# STM8S003F3P6_RF_1RELAY_LEARN_CODE.net
KiCad netlist of a schematic drawn in Altium Designer
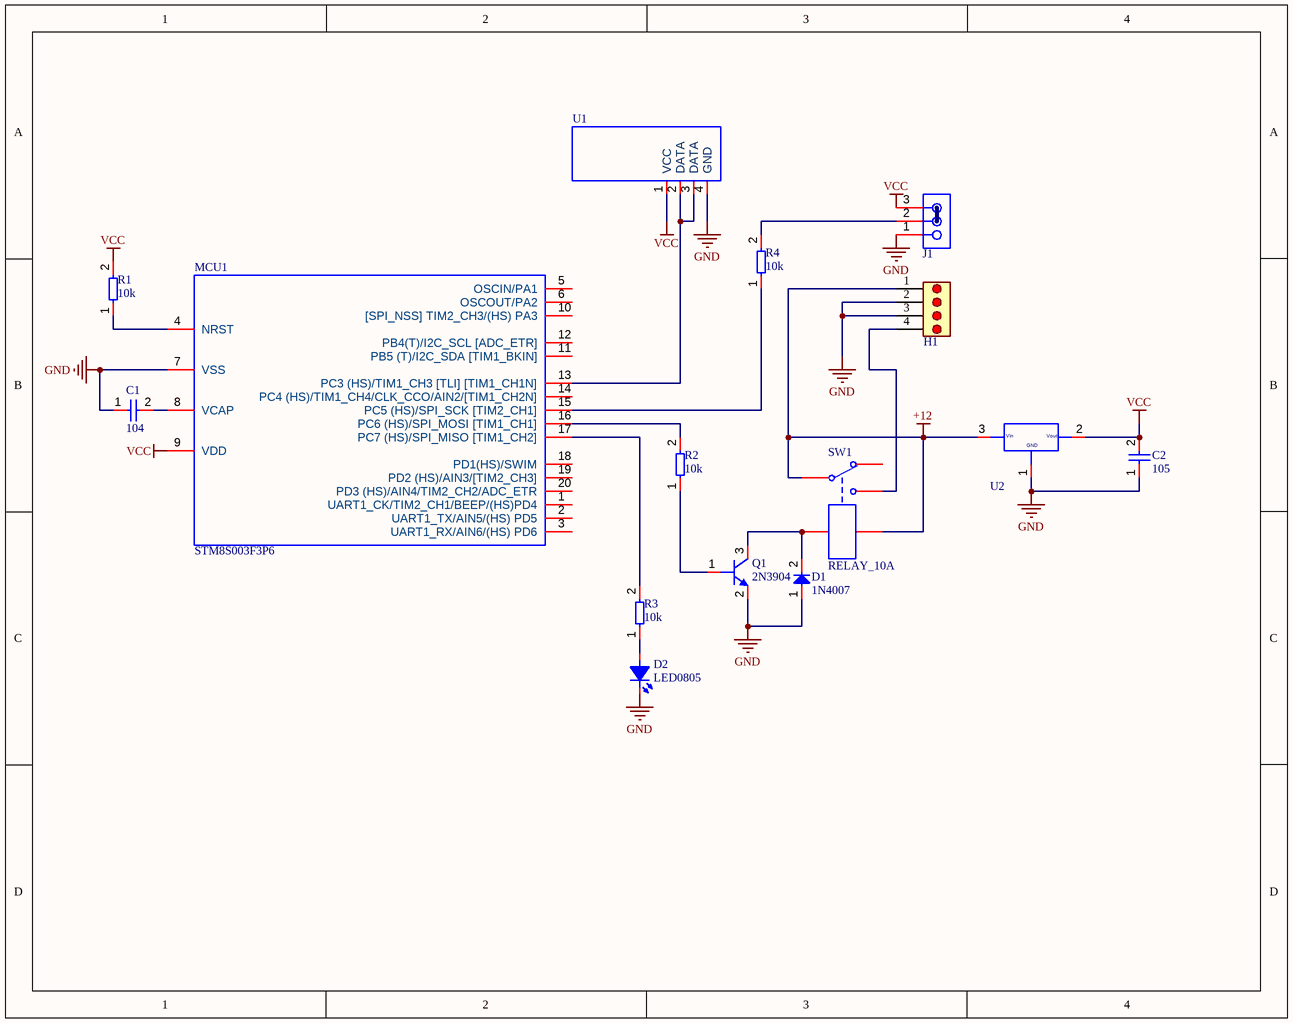
[diagram p0: STM8S003F3P6_RF_1RELAY_LEARN_CODE.SchDoc]

(export (version "E")
  (design (tool "Eeschema 10.0.6"))
  (components
    (comp (ref "C1") (value "104") (footprint "C0805") (libsource (lib "Lib31082020") (part "C0805")))
    (comp (ref "C2") (value "105") (footprint "C1206") (libsource (lib "Lib31082020") (part "C1206")))
    (comp (ref "D1")
      (value "1N4007")
      (footprint "DO-214AC(SMA)")
      (libsource (lib "Lib31082020") (part "Diode 1N4007-DO214AC(SMA)"))
    )
    (comp (ref "D2")
      (value "LED0805")
      (footprint "L0805RED")
      (libsource (lib "Lib31082020") (part "LED0805"))
    )
    (comp (ref "H1")
      (value "Header 4")
      (footprint "HEADER 4")
      (libsource (lib "Library 3D") (part "Header 4"))
    )
    (comp (ref "J1")
      (value "Header 3x1 TH Pitch 2.54mm")
      (footprint "Header 3x1 TH Pitch 2.54mm")
      (libsource (lib "Lib31082020") (part "Header 3x1 TH Pitch 2.54mm"))
    )
    (comp (ref "MCU1")
      (value "STM8S003F3P6")
      (footprint "TSSOP20_0.65_4.4")
      (libsource (lib "Lib31082020") (part "STM8S003F3P6"))
    )
    (comp (ref "Q1")
      (value "2N3904")
      (footprint "SOT23-3")
      (libsource (lib "Lib31082020") (part "2N3904 (SOT-23)"))
    )
    (comp (ref "R1") (value "10k") (footprint "R0805") (libsource (lib "Lib31082020") (part "Resistor SMD")))
    (comp (ref "R2") (value "10k") (footprint "R0805") (libsource (lib "Lib31082020") (part "Resistor SMD")))
    (comp (ref "R3") (value "10k") (footprint "R0805") (libsource (lib "Lib31082020") (part "Resistor SMD")))
    (comp (ref "R4") (value "10k") (footprint "R0805") (libsource (lib "Lib31082020") (part "Resistor SMD")))
    (comp (ref "SW1")
      (value "RELAY_10A")
      (footprint "RELAY_10A_5PIN")
      (libsource (lib "Lib31082020") (part "RELAY_10A"))
    )
    (comp (ref "U1")
      (value "RF433_315_RECEVICE")
      (footprint "RF433_315_RECEVICE")
      (libsource (lib "Lib31082020") (part "RF433_315"))
    )
    (comp (ref "U2")
      (value "AMS1117")
      (footprint "SOT223-3")
      (libsource (lib "Lib31082020") (part "AMS1117(SOT-223)"))
    )
  )
  (nets
    (net (code "1") (name "+12") (class "Default")
      (node (ref "H1") (pin "1") (pinfunction "1_1") (pintype "passive"))
      (node (ref "SW1") (pin "2") (pinfunction "2_2") (pintype "passive"))
      (node (ref "SW1") (pin "3") (pinfunction "3_3") (pintype "passive"))
      (node (ref "U2") (pin "3") (pinfunction "3_3") (pintype "passive"))
    )
    (net (code "2") (name "GND") (class "Default")
      (node (ref "C1") (pin "1") (pinfunction "1_1") (pintype "passive"))
      (node (ref "C2") (pin "1") (pinfunction "1_1") (pintype "passive"))
      (node (ref "D1") (pin "1") (pinfunction "1_1") (pintype "passive"))
      (node (ref "D2") (pin "2") (pinfunction "K_2") (pintype "passive"))
      (node (ref "H1") (pin "2") (pinfunction "2_2") (pintype "passive"))
      (node (ref "H1") (pin "3") (pinfunction "3_3") (pintype "passive"))
      (node (ref "J1") (pin "1") (pinfunction "1_1") (pintype "passive"))
      (node (ref "MCU1") (pin "7") (pinfunction "VSS_7") (pintype "passive"))
      (node (ref "Q1") (pin "2") (pinfunction "E_2") (pintype "passive"))
      (node (ref "U1") (pin "4") (pinfunction "GND_4") (pintype "passive"))
      (node (ref "U2") (pin "1") (pinfunction "1_1") (pintype "passive"))
    )
    (net (code "3") (name "Net-(D2-A)") (class "Default")
      (node (ref "D2") (pin "1") (pinfunction "A_1") (pintype "passive"))
      (node (ref "R3") (pin "1") (pinfunction "1_1") (pintype "passive"))
    )
    (net (code "4") (name "Net-(H1-Pad4)") (class "Default")
      (node (ref "H1") (pin "4") (pinfunction "4_4") (pintype "passive"))
      (node (ref "SW1") (pin "5") (pinfunction "5_5") (pintype "passive"))
    )
    (net (code "5") (name "Net-(J1-Pad2)") (class "Default")
      (node (ref "J1") (pin "2") (pinfunction "2_2") (pintype "passive"))
      (node (ref "R4") (pin "2") (pinfunction "2_2") (pintype "passive"))
    )
    (net (code "6") (name "Net-(MCU1-NRST)") (class "Default")
      (node (ref "MCU1") (pin "4") (pinfunction "NRST_4") (pintype "passive"))
      (node (ref "R1") (pin "1") (pinfunction "1_1") (pintype "passive"))
    )
    (net (code "7") (name "Net-(MCU1-PC3_(HS){slash}TIM1_CH3_[TLI]_[TIM1_CH1N])") (class "Default")
      (node (ref "MCU1") (pin "13") (pinfunction "PC3_(HS)/TIM1_CH3_[TLI]_[TIM1_CH1N]_13") (pintype "passive"))
      (node (ref "U1") (pin "2") (pinfunction "DATA_2") (pintype "passive"))
      (node (ref "U1") (pin "3") (pinfunction "DATA_3") (pintype "passive"))
    )
    (net (code "8") (name "Net-(MCU1-PC5_(HS){slash}SPI_SCK_[TIM2_CH1])") (class "Default")
      (node (ref "MCU1") (pin "15") (pinfunction "PC5_(HS)/SPI_SCK_[TIM2_CH1]_15") (pintype "passive"))
      (node (ref "R4") (pin "1") (pinfunction "1_1") (pintype "passive"))
    )
    (net (code "9") (name "Net-(MCU1-PC6_(HS){slash}SPI_MOSI_[TIM1_CH1])") (class "Default")
      (node (ref "MCU1") (pin "16") (pinfunction "PC6_(HS)/SPI_MOSI_[TIM1_CH1]_16") (pintype "passive"))
      (node (ref "R2") (pin "2") (pinfunction "2_2") (pintype "passive"))
    )
    (net (code "10") (name "Net-(MCU1-PC7_(HS){slash}SPI_MISO_[TIM1_CH2])") (class "Default")
      (node (ref "MCU1") (pin "17") (pinfunction "PC7_(HS)/SPI_MISO_[TIM1_CH2]_17") (pintype "passive"))
      (node (ref "R3") (pin "2") (pinfunction "2_2") (pintype "passive"))
    )
    (net (code "11") (name "Net-(MCU1-VCAP)") (class "Default")
      (node (ref "C1") (pin "2") (pinfunction "2_2") (pintype "passive"))
      (node (ref "MCU1") (pin "8") (pinfunction "VCAP_8") (pintype "passive"))
    )
    (net (code "12") (name "Net-(Q1-B)") (class "Default")
      (node (ref "Q1") (pin "1") (pinfunction "B_1") (pintype "passive"))
      (node (ref "R2") (pin "1") (pinfunction "1_1") (pintype "passive"))
    )
    (net (code "13") (name "Net-(Q1-C)") (class "Default")
      (node (ref "D1") (pin "2") (pinfunction "2_2") (pintype "passive"))
      (node (ref "Q1") (pin "3") (pinfunction "C_3") (pintype "passive"))
      (node (ref "SW1") (pin "1") (pinfunction "1_1") (pintype "passive"))
    )
    (net (code "14") (name "VCC") (class "Default")
      (node (ref "C2") (pin "2") (pinfunction "2_2") (pintype "passive"))
      (node (ref "J1") (pin "3") (pinfunction "3_3") (pintype "passive"))
      (node (ref "MCU1") (pin "9") (pinfunction "VDD_9") (pintype "passive"))
      (node (ref "R1") (pin "2") (pinfunction "2_2") (pintype "passive"))
      (node (ref "U1") (pin "1") (pinfunction "VCC_1") (pintype "passive"))
      (node (ref "U2") (pin "2") (pinfunction "2_2") (pintype "passive"))
    )
    (net (code "15") (name "unconnected-(MCU1-OSCIN{slash}PA1-Pad5)") (class "Default")
      (node (ref "MCU1") (pin "5") (pinfunction "OSCIN/PA1_5") (pintype "passive"))
    )
    (net (code "16") (name "unconnected-(MCU1-OSCOUT{slash}PA2-Pad6)") (class "Default")
      (node (ref "MCU1") (pin "6") (pinfunction "OSCOUT/PA2_6") (pintype "passive"))
    )
    (net (code "17") (name "unconnected-(MCU1-PB4(T){slash}I2C_SCL_[ADC_ETR]-Pad12)") (class "Default")
      (node (ref "MCU1") (pin "12") (pinfunction "PB4(T)/I2C_SCL_[ADC_ETR]_12") (pintype "passive"))
    )
    (net (code "18") (name "unconnected-(MCU1-PB5_(T){slash}I2C_SDA_[TIM1_BKIN]-Pad11)") (class "Default")
      (node (ref "MCU1") (pin "11") (pinfunction "PB5_(T)/I2C_SDA_[TIM1_BKIN]_11") (pintype "passive"))
    )
    (net (code "19") (name "unconnected-(MCU1-PC4_(HS){slash}TIM1_CH4{slash}CLK_CCO{slash}AIN2{slash}[TIM1_CH2N]-Pad14)") (class "Default")
      (node (ref "MCU1") (pin "14") (pinfunction "PC4_(HS)/TIM1_CH4/CLK_CCO/AIN2/[TIM1_CH2N]_14") (pintype "passive"))
    )
    (net (code "20") (name "unconnected-(MCU1-PD1(HS){slash}SWIM-Pad18)") (class "Default")
      (node (ref "MCU1") (pin "18") (pinfunction "PD1(HS)/SWIM_18") (pintype "passive"))
    )
    (net (code "21") (name "unconnected-(MCU1-PD2_(HS){slash}AIN3{slash}[TIM2_CH3]-Pad19)") (class "Default")
      (node (ref "MCU1") (pin "19") (pinfunction "PD2_(HS)/AIN3/[TIM2_CH3]_19") (pintype "passive"))
    )
    (net (code "22") (name "unconnected-(MCU1-PD3_(HS){slash}AIN4{slash}TIM2_CH2{slash}ADC_ETR-Pad20)") (class "Default")
      (node (ref "MCU1") (pin "20") (pinfunction "PD3_(HS)/AIN4/TIM2_CH2/ADC_ETR_20") (pintype "passive"))
    )
    (net (code "23") (name "unconnected-(MCU1-UART1_CK{slash}TIM2_CH1{slash}BEEP{slash}(HS)PD4-Pad1)") (class "Default")
      (node (ref "MCU1") (pin "1") (pinfunction "UART1_CK/TIM2_CH1/BEEP/(HS)PD4_1") (pintype "passive"))
    )
    (net (code "24") (name "unconnected-(MCU1-UART1_RX{slash}AIN6{slash}(HS)_PD6-Pad3)") (class "Default")
      (node (ref "MCU1") (pin "3") (pinfunction "UART1_RX/AIN6/(HS)_PD6_3") (pintype "passive"))
    )
    (net (code "25") (name "unconnected-(MCU1-UART1_TX{slash}AIN5{slash}(HS)_PD5-Pad2)") (class "Default")
      (node (ref "MCU1") (pin "2") (pinfunction "UART1_TX/AIN5/(HS)_PD5_2") (pintype "passive"))
    )
    (net (code "26") (name "unconnected-(MCU1-[SPI_NSS]_TIM2_CH3{slash}(HS)_PA3-Pad10)") (class "Default")
      (node (ref "MCU1") (pin "10") (pinfunction "[SPI_NSS]_TIM2_CH3/(HS)_PA3_10") (pintype "passive"))
    )
    (net (code "27") (name "unconnected-(SW1-Pad4)") (class "Default")
      (node (ref "SW1") (pin "4") (pinfunction "4_4") (pintype "passive"))
    )
  )
)
